# Breadboard-ATMEGA328.net
KiCad netlist of a schematic drawn in EAGLE
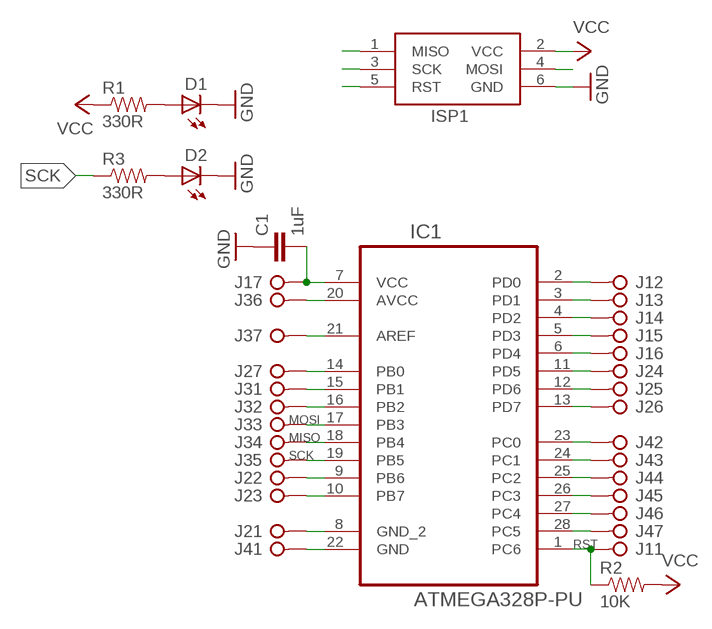
[diagram p0: schematic, sheet 1]

(export (version "E")
  (design (tool "Eeschema 10.0.6"))
  (components
    (comp (ref "C1")
      (value "1uF")
      (footprint "eagle-import:CAPACITOR-0805")
      (libsource (lib "eagle-import") (part "CAPACITOR-0805"))
    )
    (comp (ref "D1")
      (value "LED-0805")
      (footprint "eagle-import:LED-0805")
      (libsource (lib "eagle-import") (part "LED-0805"))
    )
    (comp (ref "D2")
      (value "LED-0805")
      (footprint "eagle-import:LED-0805")
      (libsource (lib "eagle-import") (part "LED-0805"))
    )
    (comp (ref "IC1")
      (value "ATMEGA328P-PU")
      (footprint "eagle-import:DIP28")
      (libsource (lib "eagle-import") (part "ATMEGA328P-PU"))
    )
    (comp (ref "ISP1")
      (value "ICSP-HEADER-6")
      (footprint "eagle-import:ICSP-HEADER")
      (libsource (lib "eagle-import") (part "ICSP-HEADER-6"))
    )
    (comp (ref "J1")
      (value "PINHD-1X7")
      (footprint "eagle-import:1X07")
      (libsource (lib "eagle-import") (part "PINHD-1X7"))
    )
    (comp (ref "J2")
      (value "PINHD-1X7")
      (footprint "eagle-import:1X07")
      (libsource (lib "eagle-import") (part "PINHD-1X7"))
    )
    (comp (ref "J3")
      (value "PINHD-1X7")
      (footprint "eagle-import:1X07")
      (libsource (lib "eagle-import") (part "PINHD-1X7"))
    )
    (comp (ref "J4")
      (value "PINHD-1X7")
      (footprint "eagle-import:1X07")
      (libsource (lib "eagle-import") (part "PINHD-1X7"))
    )
    (comp (ref "R1")
      (value "330R")
      (footprint "eagle-import:RESISTOR-0805")
      (libsource (lib "eagle-import") (part "RESISTOR-0805"))
    )
    (comp (ref "R2")
      (value "10K")
      (footprint "eagle-import:RESISTOR-0805")
      (libsource (lib "eagle-import") (part "RESISTOR-0805"))
    )
    (comp (ref "R3")
      (value "330R")
      (footprint "eagle-import:RESISTOR-0805")
      (libsource (lib "eagle-import") (part "RESISTOR-0805"))
    )
  )
  (nets
    (net (code "1") (name "/MISO") (class "Default")
      (node (ref "IC1") (pin "18") (pinfunction "PB4_18") (pintype "bidirectional"))
      (node (ref "ISP1") (pin "1") (pinfunction "MISO_1") (pintype "input"))
      (node (ref "J3") (pin "4") (pinfunction "KL_4") (pintype "passive"))
    )
    (net (code "2") (name "/MOSI") (class "Default")
      (node (ref "IC1") (pin "17") (pinfunction "PB3_17") (pintype "bidirectional"))
      (node (ref "ISP1") (pin "4") (pinfunction "MOSI_4") (pintype "output"))
      (node (ref "J3") (pin "3") (pinfunction "KL_3") (pintype "passive"))
    )
    (net (code "3") (name "/RST") (class "Default")
      (node (ref "IC1") (pin "1") (pinfunction "PC6_1") (pintype "bidirectional"))
      (node (ref "ISP1") (pin "5") (pinfunction "RST_5") (pintype "output"))
      (node (ref "J1") (pin "1") (pinfunction "KL_1") (pintype "passive"))
      (node (ref "R2") (pin "1") (pinfunction "1_1") (pintype "passive"))
    )
    (net (code "4") (name "GND") (class "Default")
      (node (ref "C1") (pin "1") (pinfunction "1_1") (pintype "passive"))
      (node (ref "D1") (pin "2") (pinfunction "C_2") (pintype "passive"))
      (node (ref "D2") (pin "2") (pinfunction "C_2") (pintype "passive"))
      (node (ref "IC1") (pin "8") (pinfunction "GND_2_8") (pintype "passive"))
      (node (ref "ISP1") (pin "6") (pinfunction "GND_6") (pintype "power_in"))
      (node (ref "J2") (pin "1") (pinfunction "KL_1") (pintype "passive"))
    )
    (net (code "5") (name "Net-(D1-A)") (class "Default")
      (node (ref "D1") (pin "1") (pinfunction "A_1") (pintype "passive"))
      (node (ref "R1") (pin "2") (pinfunction "2_2") (pintype "passive"))
    )
    (net (code "6") (name "Net-(D2-A)") (class "Default")
      (node (ref "D2") (pin "1") (pinfunction "A_1") (pintype "passive"))
      (node (ref "R3") (pin "2") (pinfunction "2_2") (pintype "passive"))
    )
    (net (code "7") (name "Net-(IC1-AREF)") (class "Default")
      (node (ref "IC1") (pin "21") (pinfunction "AREF_21") (pintype "input"))
      (node (ref "J3") (pin "7") (pinfunction "KL_7") (pintype "passive"))
    )
    (net (code "8") (name "Net-(IC1-GND)") (class "Default")
      (node (ref "IC1") (pin "22") (pinfunction "GND_22") (pintype "passive"))
      (node (ref "J4") (pin "1") (pinfunction "KL_1") (pintype "passive"))
    )
    (net (code "9") (name "Net-(IC1-PB0)") (class "Default")
      (node (ref "IC1") (pin "14") (pinfunction "PB0_14") (pintype "bidirectional"))
      (node (ref "J2") (pin "7") (pinfunction "KL_7") (pintype "passive"))
    )
    (net (code "10") (name "Net-(IC1-PB1)") (class "Default")
      (node (ref "IC1") (pin "15") (pinfunction "PB1_15") (pintype "bidirectional"))
      (node (ref "J3") (pin "1") (pinfunction "KL_1") (pintype "passive"))
    )
    (net (code "11") (name "Net-(IC1-PB2)") (class "Default")
      (node (ref "IC1") (pin "16") (pinfunction "PB2_16") (pintype "bidirectional"))
      (node (ref "J3") (pin "2") (pinfunction "KL_2") (pintype "passive"))
    )
    (net (code "12") (name "Net-(IC1-PB6)") (class "Default")
      (node (ref "IC1") (pin "9") (pinfunction "PB6_9") (pintype "bidirectional"))
      (node (ref "J2") (pin "2") (pinfunction "KL_2") (pintype "passive"))
    )
    (net (code "13") (name "Net-(IC1-PB7)") (class "Default")
      (node (ref "IC1") (pin "10") (pinfunction "PB7_10") (pintype "bidirectional"))
      (node (ref "J2") (pin "3") (pinfunction "KL_3") (pintype "passive"))
    )
    (net (code "14") (name "Net-(IC1-PC0)") (class "Default")
      (node (ref "IC1") (pin "23") (pinfunction "PC0_23") (pintype "bidirectional"))
      (node (ref "J4") (pin "2") (pinfunction "KL_2") (pintype "passive"))
    )
    (net (code "15") (name "Net-(IC1-PC1)") (class "Default")
      (node (ref "IC1") (pin "24") (pinfunction "PC1_24") (pintype "bidirectional"))
      (node (ref "J4") (pin "3") (pinfunction "KL_3") (pintype "passive"))
    )
    (net (code "16") (name "Net-(IC1-PC2)") (class "Default")
      (node (ref "IC1") (pin "25") (pinfunction "PC2_25") (pintype "bidirectional"))
      (node (ref "J4") (pin "4") (pinfunction "KL_4") (pintype "passive"))
    )
    (net (code "17") (name "Net-(IC1-PC3)") (class "Default")
      (node (ref "IC1") (pin "26") (pinfunction "PC3_26") (pintype "bidirectional"))
      (node (ref "J4") (pin "5") (pinfunction "KL_5") (pintype "passive"))
    )
    (net (code "18") (name "Net-(IC1-PC4)") (class "Default")
      (node (ref "IC1") (pin "27") (pinfunction "PC4_27") (pintype "bidirectional"))
      (node (ref "J4") (pin "6") (pinfunction "KL_6") (pintype "passive"))
    )
    (net (code "19") (name "Net-(IC1-PC5)") (class "Default")
      (node (ref "IC1") (pin "28") (pinfunction "PC5_28") (pintype "bidirectional"))
      (node (ref "J4") (pin "7") (pinfunction "KL_7") (pintype "passive"))
    )
    (net (code "20") (name "Net-(IC1-PD0)") (class "Default")
      (node (ref "IC1") (pin "2") (pinfunction "PD0_2") (pintype "bidirectional"))
      (node (ref "J1") (pin "2") (pinfunction "KL_2") (pintype "passive"))
    )
    (net (code "21") (name "Net-(IC1-PD1)") (class "Default")
      (node (ref "IC1") (pin "3") (pinfunction "PD1_3") (pintype "bidirectional"))
      (node (ref "J1") (pin "3") (pinfunction "KL_3") (pintype "passive"))
    )
    (net (code "22") (name "Net-(IC1-PD2)") (class "Default")
      (node (ref "IC1") (pin "4") (pinfunction "PD2_4") (pintype "bidirectional"))
      (node (ref "J1") (pin "4") (pinfunction "KL_4") (pintype "passive"))
    )
    (net (code "23") (name "Net-(IC1-PD3)") (class "Default")
      (node (ref "IC1") (pin "5") (pinfunction "PD3_5") (pintype "bidirectional"))
      (node (ref "J1") (pin "5") (pinfunction "KL_5") (pintype "passive"))
    )
    (net (code "24") (name "Net-(IC1-PD4)") (class "Default")
      (node (ref "IC1") (pin "6") (pinfunction "PD4_6") (pintype "bidirectional"))
      (node (ref "J1") (pin "6") (pinfunction "KL_6") (pintype "passive"))
    )
    (net (code "25") (name "Net-(IC1-PD5)") (class "Default")
      (node (ref "IC1") (pin "11") (pinfunction "PD5_11") (pintype "bidirectional"))
      (node (ref "J2") (pin "4") (pinfunction "KL_4") (pintype "passive"))
    )
    (net (code "26") (name "Net-(IC1-PD6)") (class "Default")
      (node (ref "IC1") (pin "12") (pinfunction "PD6_12") (pintype "bidirectional"))
      (node (ref "J2") (pin "5") (pinfunction "KL_5") (pintype "passive"))
    )
    (net (code "27") (name "Net-(IC1-PD7)") (class "Default")
      (node (ref "IC1") (pin "13") (pinfunction "PD7_13") (pintype "bidirectional"))
      (node (ref "J2") (pin "6") (pinfunction "KL_6") (pintype "passive"))
    )
    (net (code "28") (name "SCK") (class "Default")
      (node (ref "IC1") (pin "19") (pinfunction "PB5_19") (pintype "bidirectional"))
      (node (ref "ISP1") (pin "3") (pinfunction "SCK_3") (pintype "output"))
      (node (ref "J3") (pin "5") (pinfunction "KL_5") (pintype "passive"))
      (node (ref "R3") (pin "1") (pinfunction "1_1") (pintype "passive"))
    )
    (net (code "29") (name "VCC") (class "Default")
      (node (ref "C1") (pin "2") (pinfunction "2_2") (pintype "passive"))
      (node (ref "IC1") (pin "20") (pinfunction "AVCC_20") (pintype "power_in"))
      (node (ref "IC1") (pin "7") (pinfunction "VCC_7") (pintype "power_in"))
      (node (ref "ISP1") (pin "2") (pinfunction "VCC_2") (pintype "power_in"))
      (node (ref "J1") (pin "7") (pinfunction "KL_7") (pintype "passive"))
      (node (ref "J3") (pin "6") (pinfunction "KL_6") (pintype "passive"))
      (node (ref "R1") (pin "1") (pinfunction "1_1") (pintype "passive"))
      (node (ref "R2") (pin "2") (pinfunction "2_2") (pintype "passive"))
    )
  )
)
